# radio_module.net
KiCad netlist of a schematic drawn in EAGLE
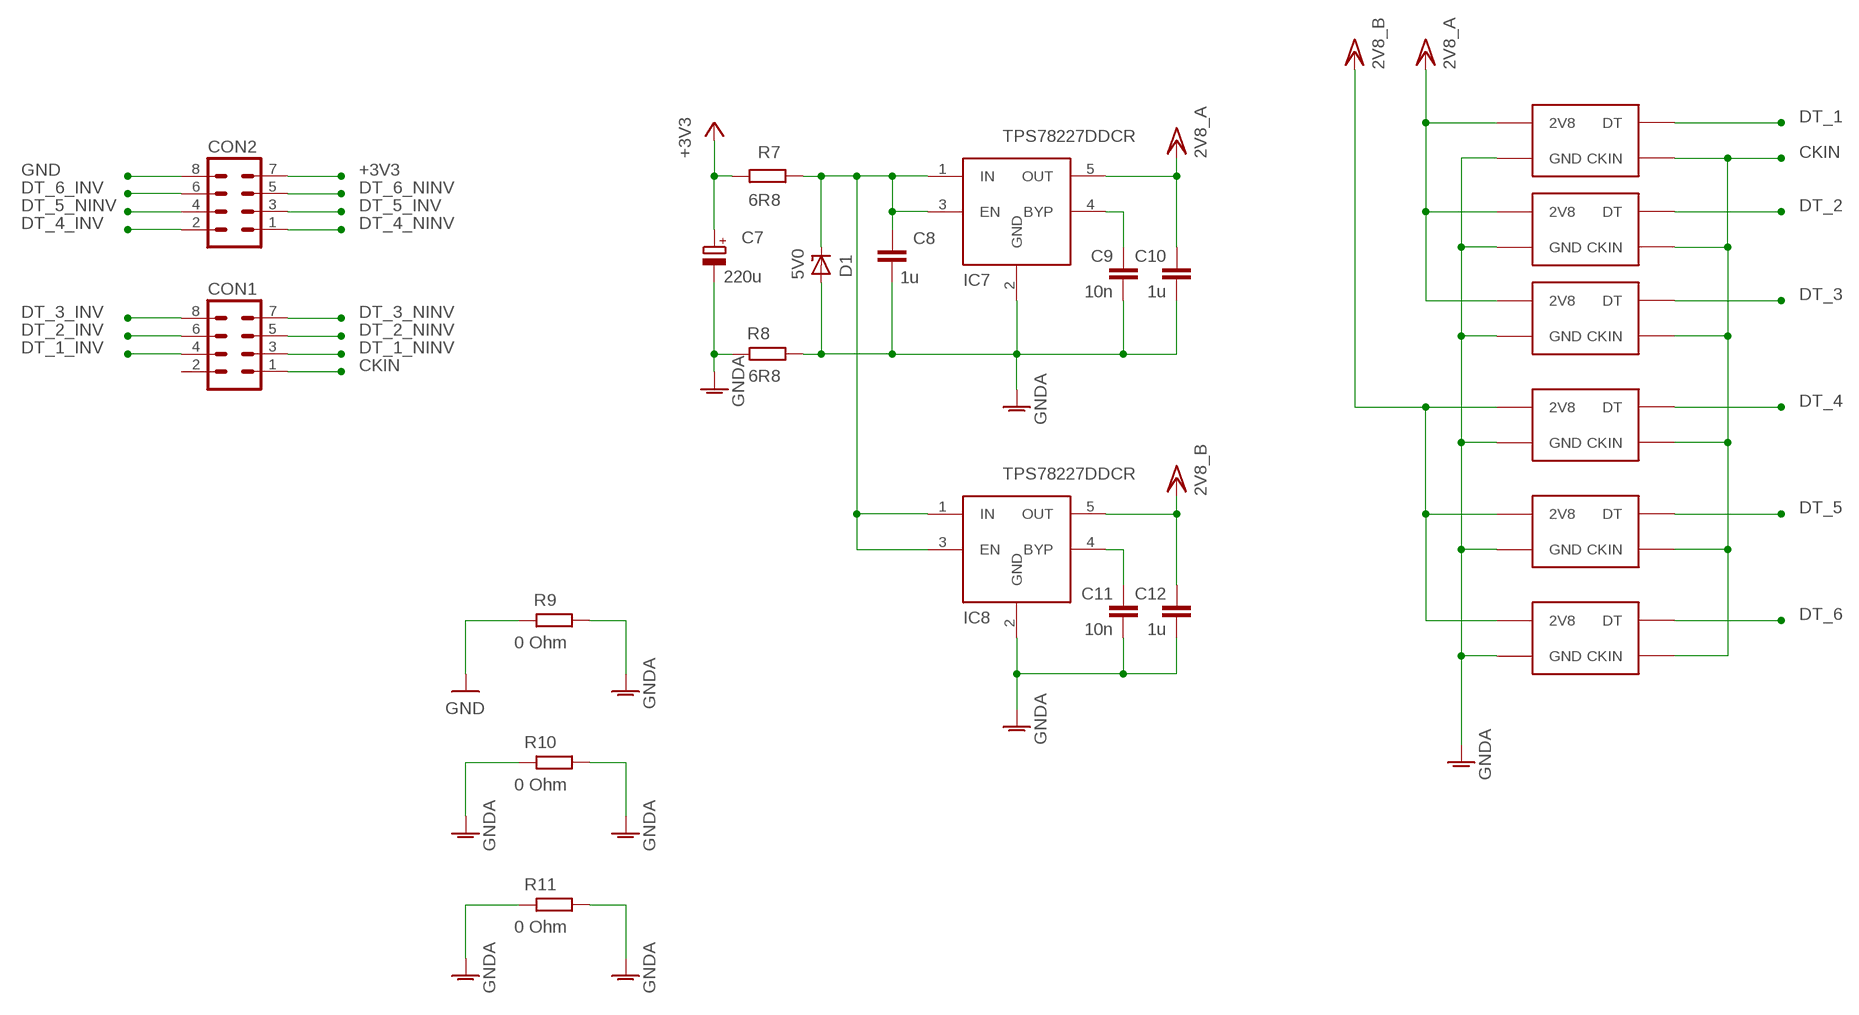
[diagram p0: schematic, sheet 1, part 1 of 2]
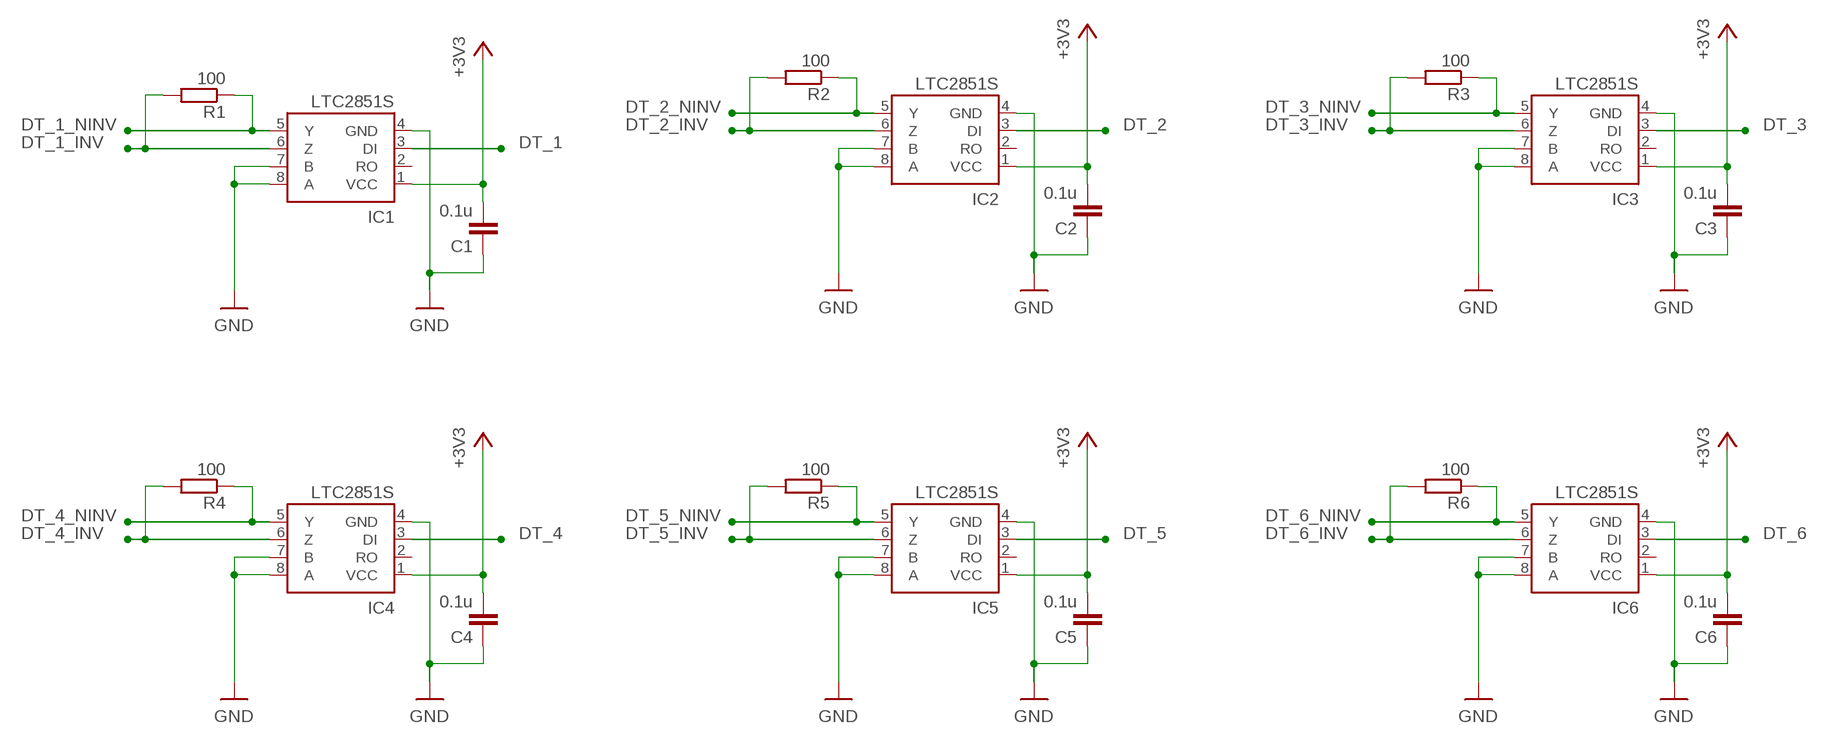
[diagram p1: schematic, sheet 1, part 2 of 2]

(export (version "E")
  (design (tool "Eeschema 10.0.6"))
  (components
    (comp (ref "C1")
      (value "0.1u")
      (footprint "eagle-import:C0805")
      (libsource (lib "eagle-import") (part "C-EUC0805"))
    )
    (comp (ref "C2")
      (value "0.1u")
      (footprint "eagle-import:C0805")
      (libsource (lib "eagle-import") (part "C-EUC0805"))
    )
    (comp (ref "C3")
      (value "0.1u")
      (footprint "eagle-import:C0805")
      (libsource (lib "eagle-import") (part "C-EUC0805"))
    )
    (comp (ref "C4")
      (value "0.1u")
      (footprint "eagle-import:C0805")
      (libsource (lib "eagle-import") (part "C-EUC0805"))
    )
    (comp (ref "C5")
      (value "0.1u")
      (footprint "eagle-import:C0805")
      (libsource (lib "eagle-import") (part "C-EUC0805"))
    )
    (comp (ref "C6")
      (value "0.1u")
      (footprint "eagle-import:C0805")
      (libsource (lib "eagle-import") (part "C-EUC0805"))
    )
    (comp (ref "C7")
      (value "220u")
      (footprint "eagle-import:C1210")
      (libsource (lib "eagle-import") (part "CPOL-EU1210"))
    )
    (comp (ref "C8")
      (value "1u")
      (footprint "eagle-import:C0603")
      (libsource (lib "eagle-import") (part "C-EUC0603"))
    )
    (comp (ref "C9")
      (value "10n")
      (footprint "eagle-import:C0603")
      (libsource (lib "eagle-import") (part "C-EUC0603"))
    )
    (comp (ref "C10")
      (value "1u")
      (footprint "eagle-import:C0603")
      (libsource (lib "eagle-import") (part "C-EUC0603"))
    )
    (comp (ref "C11")
      (value "10n")
      (footprint "eagle-import:C0603")
      (libsource (lib "eagle-import") (part "C-EUC0603"))
    )
    (comp (ref "C12")
      (value "1u")
      (footprint "eagle-import:C0603")
      (libsource (lib "eagle-import") (part "C-EUC0603"))
    )
    (comp (ref "CON1")
      (value "MA04-2")
      (footprint "eagle-import:MA04-2")
      (libsource (lib "eagle-import") (part "MA04-2"))
    )
    (comp (ref "CON2")
      (value "MA04-2")
      (footprint "eagle-import:MA04-2")
      (libsource (lib "eagle-import") (part "MA04-2"))
    )
    (comp (ref "D1")
      (value "5V0")
      (footprint "eagle-import:SOD523")
      (libsource (lib "eagle-import") (part "ZENER-DIODESOD523"))
    )
    (comp (ref "IC1")
      (value "LTC2851S")
      (footprint "eagle-import:SOIC8")
      (libsource (lib "eagle-import") (part "LTC2851S"))
    )
    (comp (ref "IC2")
      (value "LTC2851S")
      (footprint "eagle-import:SOIC8")
      (libsource (lib "eagle-import") (part "LTC2851S"))
    )
    (comp (ref "IC3")
      (value "LTC2851S")
      (footprint "eagle-import:SOIC8")
      (libsource (lib "eagle-import") (part "LTC2851S"))
    )
    (comp (ref "IC4")
      (value "LTC2851S")
      (footprint "eagle-import:SOIC8")
      (libsource (lib "eagle-import") (part "LTC2851S"))
    )
    (comp (ref "IC5")
      (value "LTC2851S")
      (footprint "eagle-import:SOIC8")
      (libsource (lib "eagle-import") (part "LTC2851S"))
    )
    (comp (ref "IC6")
      (value "LTC2851S")
      (footprint "eagle-import:SOIC8")
      (libsource (lib "eagle-import") (part "LTC2851S"))
    )
    (comp (ref "IC7")
      (value "TPS78227DDCR")
      (footprint "eagle-import:SOT23-5")
      (libsource (lib "eagle-import") (part "NCP700BSN"))
    )
    (comp (ref "IC8")
      (value "TPS78227DDCR")
      (footprint "eagle-import:SOT23-5")
      (libsource (lib "eagle-import") (part "NCP700BSN"))
    )
    (comp (ref "MOD_1")
      (value "GPS_RADIO_MODULE")
      (footprint "eagle-import:GPS_RADIO_MODULE")
      (libsource (lib "eagle-import") (part "GPS_RADIO_MODULE"))
    )
    (comp (ref "MOD_2")
      (value "GPS_RADIO_MODULE")
      (footprint "eagle-import:GPS_RADIO_MODULE")
      (libsource (lib "eagle-import") (part "GPS_RADIO_MODULE"))
    )
    (comp (ref "MOD_3")
      (value "GPS_RADIO_MODULE")
      (footprint "eagle-import:GPS_RADIO_MODULE")
      (libsource (lib "eagle-import") (part "GPS_RADIO_MODULE"))
    )
    (comp (ref "MOD_4")
      (value "GPS_RADIO_MODULE")
      (footprint "eagle-import:GPS_RADIO_MODULE")
      (libsource (lib "eagle-import") (part "GPS_RADIO_MODULE"))
    )
    (comp (ref "MOD_5")
      (value "GPS_RADIO_MODULE")
      (footprint "eagle-import:GPS_RADIO_MODULE")
      (libsource (lib "eagle-import") (part "GPS_RADIO_MODULE"))
    )
    (comp (ref "MOD_6")
      (value "GPS_RADIO_MODULE")
      (footprint "eagle-import:GPS_RADIO_MODULE")
      (libsource (lib "eagle-import") (part "GPS_RADIO_MODULE"))
    )
    (comp (ref "R1")
      (value "100")
      (footprint "eagle-import:R0603")
      (libsource (lib "eagle-import") (part "R-EU_R0603"))
    )
    (comp (ref "R2")
      (value "100")
      (footprint "eagle-import:R0603")
      (libsource (lib "eagle-import") (part "R-EU_R0603"))
    )
    (comp (ref "R3")
      (value "100")
      (footprint "eagle-import:R0603")
      (libsource (lib "eagle-import") (part "R-EU_R0603"))
    )
    (comp (ref "R4")
      (value "100")
      (footprint "eagle-import:R0603")
      (libsource (lib "eagle-import") (part "R-EU_R0603"))
    )
    (comp (ref "R5")
      (value "100")
      (footprint "eagle-import:R0603")
      (libsource (lib "eagle-import") (part "R-EU_R0603"))
    )
    (comp (ref "R6")
      (value "100")
      (footprint "eagle-import:R0603")
      (libsource (lib "eagle-import") (part "R-EU_R0603"))
    )
    (comp (ref "R7")
      (value "6R8")
      (footprint "eagle-import:R0805")
      (libsource (lib "eagle-import") (part "R-EU_R0805"))
    )
    (comp (ref "R8")
      (value "6R8")
      (footprint "eagle-import:R0603")
      (libsource (lib "eagle-import") (part "R-EU_R0603"))
    )
    (comp (ref "R9")
      (value "0 Ohm")
      (footprint "eagle-import:R0805")
      (libsource (lib "eagle-import") (part "R-EU_R0805"))
    )
    (comp (ref "R10")
      (value "0 Ohm")
      (footprint "eagle-import:R0805")
      (libsource (lib "eagle-import") (part "R-EU_R0805"))
    )
    (comp (ref "R11")
      (value "0 Ohm")
      (footprint "eagle-import:R0805")
      (libsource (lib "eagle-import") (part "R-EU_R0805"))
    )
  )
  (nets
    (net (code "1") (name "+3V3") (class "Default")
      (node (ref "C1") (pin "2") (pinfunction "2_2") (pintype "passive"))
      (node (ref "C2") (pin "2") (pinfunction "2_2") (pintype "passive"))
      (node (ref "C3") (pin "2") (pinfunction "2_2") (pintype "passive"))
      (node (ref "C4") (pin "2") (pinfunction "2_2") (pintype "passive"))
      (node (ref "C5") (pin "2") (pinfunction "2_2") (pintype "passive"))
      (node (ref "C6") (pin "2") (pinfunction "2_2") (pintype "passive"))
      (node (ref "C7") (pin "1") (pinfunction "+_1") (pintype "passive"))
      (node (ref "CON2") (pin "7") (pinfunction "7_7") (pintype "passive"))
      (node (ref "IC1") (pin "1") (pinfunction "VCC_1") (pintype "power_in"))
      (node (ref "IC2") (pin "1") (pinfunction "VCC_1") (pintype "power_in"))
      (node (ref "IC3") (pin "1") (pinfunction "VCC_1") (pintype "power_in"))
      (node (ref "IC4") (pin "1") (pinfunction "VCC_1") (pintype "power_in"))
      (node (ref "IC5") (pin "1") (pinfunction "VCC_1") (pintype "power_in"))
      (node (ref "IC6") (pin "1") (pinfunction "VCC_1") (pintype "power_in"))
      (node (ref "R7") (pin "2") (pinfunction "2_2") (pintype "passive"))
    )
    (net (code "2") (name "/CKIN") (class "Default")
      (node (ref "CON1") (pin "1") (pinfunction "1_1") (pintype "passive"))
      (node (ref "MOD_1") (pin "CKIN@13") (pinfunction "CKIN_CKIN@13") (pintype "input"))
      (node (ref "MOD_2") (pin "CKIN@13") (pinfunction "CKIN_CKIN@13") (pintype "input"))
      (node (ref "MOD_3") (pin "CKIN@13") (pinfunction "CKIN_CKIN@13") (pintype "input"))
      (node (ref "MOD_4") (pin "CKIN@13") (pinfunction "CKIN_CKIN@13") (pintype "input"))
      (node (ref "MOD_5") (pin "CKIN@13") (pinfunction "CKIN_CKIN@13") (pintype "input"))
      (node (ref "MOD_6") (pin "CKIN@13") (pinfunction "CKIN_CKIN@13") (pintype "input"))
    )
    (net (code "3") (name "/DT_1") (class "Default")
      (node (ref "IC1") (pin "3") (pinfunction "DI_3") (pintype "input"))
      (node (ref "MOD_1") (pin "DT@12") (pinfunction "DT_DT@12") (pintype "output"))
    )
    (net (code "4") (name "/DT_1_INV") (class "Default")
      (node (ref "CON1") (pin "4") (pinfunction "4_4") (pintype "passive"))
      (node (ref "IC1") (pin "6") (pinfunction "Z_6") (pintype "output"))
      (node (ref "R1") (pin "2") (pinfunction "2_2") (pintype "passive"))
    )
    (net (code "5") (name "/DT_1_NINV") (class "Default")
      (node (ref "CON1") (pin "3") (pinfunction "3_3") (pintype "passive"))
      (node (ref "IC1") (pin "5") (pinfunction "Y_5") (pintype "output"))
      (node (ref "R1") (pin "1") (pinfunction "1_1") (pintype "passive"))
    )
    (net (code "6") (name "/DT_2") (class "Default")
      (node (ref "IC2") (pin "3") (pinfunction "DI_3") (pintype "input"))
      (node (ref "MOD_2") (pin "DT@12") (pinfunction "DT_DT@12") (pintype "output"))
    )
    (net (code "7") (name "/DT_2_INV") (class "Default")
      (node (ref "CON1") (pin "6") (pinfunction "6_6") (pintype "passive"))
      (node (ref "IC2") (pin "6") (pinfunction "Z_6") (pintype "output"))
      (node (ref "R2") (pin "2") (pinfunction "2_2") (pintype "passive"))
    )
    (net (code "8") (name "/DT_2_NINV") (class "Default")
      (node (ref "CON1") (pin "5") (pinfunction "5_5") (pintype "passive"))
      (node (ref "IC2") (pin "5") (pinfunction "Y_5") (pintype "output"))
      (node (ref "R2") (pin "1") (pinfunction "1_1") (pintype "passive"))
    )
    (net (code "9") (name "/DT_3") (class "Default")
      (node (ref "IC3") (pin "3") (pinfunction "DI_3") (pintype "input"))
      (node (ref "MOD_3") (pin "DT@12") (pinfunction "DT_DT@12") (pintype "output"))
    )
    (net (code "10") (name "/DT_3_INV") (class "Default")
      (node (ref "CON1") (pin "8") (pinfunction "8_8") (pintype "passive"))
      (node (ref "IC3") (pin "6") (pinfunction "Z_6") (pintype "output"))
      (node (ref "R3") (pin "2") (pinfunction "2_2") (pintype "passive"))
    )
    (net (code "11") (name "/DT_3_NINV") (class "Default")
      (node (ref "CON1") (pin "7") (pinfunction "7_7") (pintype "passive"))
      (node (ref "IC3") (pin "5") (pinfunction "Y_5") (pintype "output"))
      (node (ref "R3") (pin "1") (pinfunction "1_1") (pintype "passive"))
    )
    (net (code "12") (name "/DT_4") (class "Default")
      (node (ref "IC4") (pin "3") (pinfunction "DI_3") (pintype "input"))
      (node (ref "MOD_6") (pin "DT@12") (pinfunction "DT_DT@12") (pintype "output"))
    )
    (net (code "13") (name "/DT_4_INV") (class "Default")
      (node (ref "CON2") (pin "2") (pinfunction "2_2") (pintype "passive"))
      (node (ref "IC4") (pin "6") (pinfunction "Z_6") (pintype "output"))
      (node (ref "R4") (pin "2") (pinfunction "2_2") (pintype "passive"))
    )
    (net (code "14") (name "/DT_4_NINV") (class "Default")
      (node (ref "CON2") (pin "1") (pinfunction "1_1") (pintype "passive"))
      (node (ref "IC4") (pin "5") (pinfunction "Y_5") (pintype "output"))
      (node (ref "R4") (pin "1") (pinfunction "1_1") (pintype "passive"))
    )
    (net (code "15") (name "/DT_5") (class "Default")
      (node (ref "IC5") (pin "3") (pinfunction "DI_3") (pintype "input"))
      (node (ref "MOD_5") (pin "DT@12") (pinfunction "DT_DT@12") (pintype "output"))
    )
    (net (code "16") (name "/DT_5_INV") (class "Default")
      (node (ref "CON2") (pin "3") (pinfunction "3_3") (pintype "passive"))
      (node (ref "IC5") (pin "6") (pinfunction "Z_6") (pintype "output"))
      (node (ref "R5") (pin "2") (pinfunction "2_2") (pintype "passive"))
    )
    (net (code "17") (name "/DT_5_NINV") (class "Default")
      (node (ref "CON2") (pin "4") (pinfunction "4_4") (pintype "passive"))
      (node (ref "IC5") (pin "5") (pinfunction "Y_5") (pintype "output"))
      (node (ref "R5") (pin "1") (pinfunction "1_1") (pintype "passive"))
    )
    (net (code "18") (name "/DT_6") (class "Default")
      (node (ref "IC6") (pin "3") (pinfunction "DI_3") (pintype "input"))
      (node (ref "MOD_4") (pin "DT@12") (pinfunction "DT_DT@12") (pintype "output"))
    )
    (net (code "19") (name "/DT_6_INV") (class "Default")
      (node (ref "CON2") (pin "6") (pinfunction "6_6") (pintype "passive"))
      (node (ref "IC6") (pin "6") (pinfunction "Z_6") (pintype "output"))
      (node (ref "R6") (pin "2") (pinfunction "2_2") (pintype "passive"))
    )
    (net (code "20") (name "/DT_6_NINV") (class "Default")
      (node (ref "CON2") (pin "5") (pinfunction "5_5") (pintype "passive"))
      (node (ref "IC6") (pin "5") (pinfunction "Y_5") (pintype "output"))
      (node (ref "R6") (pin "1") (pinfunction "1_1") (pintype "passive"))
    )
    (net (code "21") (name "2V8_A") (class "Default")
      (node (ref "C10") (pin "1") (pinfunction "1_1") (pintype "passive"))
      (node (ref "IC7") (pin "5") (pinfunction "OUT_5") (pintype "power_in"))
      (node (ref "MOD_1") (pin "2V8@11") (pinfunction "2V8_2V8@11") (pintype "power_in"))
      (node (ref "MOD_1") (pin "2V8@15") (pinfunction "2V8_2V8@15") (pintype "power_in"))
      (node (ref "MOD_1") (pin "2V8@16") (pinfunction "2V8_2V8@16") (pintype "power_in"))
      (node (ref "MOD_2") (pin "2V8@11") (pinfunction "2V8_2V8@11") (pintype "power_in"))
      (node (ref "MOD_2") (pin "2V8@15") (pinfunction "2V8_2V8@15") (pintype "power_in"))
      (node (ref "MOD_2") (pin "2V8@16") (pinfunction "2V8_2V8@16") (pintype "power_in"))
      (node (ref "MOD_3") (pin "2V8@11") (pinfunction "2V8_2V8@11") (pintype "power_in"))
      (node (ref "MOD_3") (pin "2V8@15") (pinfunction "2V8_2V8@15") (pintype "power_in"))
      (node (ref "MOD_3") (pin "2V8@16") (pinfunction "2V8_2V8@16") (pintype "power_in"))
    )
    (net (code "22") (name "2V8_B") (class "Default")
      (node (ref "C12") (pin "1") (pinfunction "1_1") (pintype "passive"))
      (node (ref "IC8") (pin "5") (pinfunction "OUT_5") (pintype "power_in"))
      (node (ref "MOD_4") (pin "2V8@11") (pinfunction "2V8_2V8@11") (pintype "power_in"))
      (node (ref "MOD_4") (pin "2V8@15") (pinfunction "2V8_2V8@15") (pintype "power_in"))
      (node (ref "MOD_4") (pin "2V8@16") (pinfunction "2V8_2V8@16") (pintype "power_in"))
      (node (ref "MOD_5") (pin "2V8@11") (pinfunction "2V8_2V8@11") (pintype "power_in"))
      (node (ref "MOD_5") (pin "2V8@15") (pinfunction "2V8_2V8@15") (pintype "power_in"))
      (node (ref "MOD_5") (pin "2V8@16") (pinfunction "2V8_2V8@16") (pintype "power_in"))
      (node (ref "MOD_6") (pin "2V8@11") (pinfunction "2V8_2V8@11") (pintype "power_in"))
      (node (ref "MOD_6") (pin "2V8@15") (pinfunction "2V8_2V8@15") (pintype "power_in"))
      (node (ref "MOD_6") (pin "2V8@16") (pinfunction "2V8_2V8@16") (pintype "power_in"))
    )
    (net (code "23") (name "GND") (class "Default")
      (node (ref "C1") (pin "1") (pinfunction "1_1") (pintype "passive"))
      (node (ref "C2") (pin "1") (pinfunction "1_1") (pintype "passive"))
      (node (ref "C3") (pin "1") (pinfunction "1_1") (pintype "passive"))
      (node (ref "C4") (pin "1") (pinfunction "1_1") (pintype "passive"))
      (node (ref "C5") (pin "1") (pinfunction "1_1") (pintype "passive"))
      (node (ref "C6") (pin "1") (pinfunction "1_1") (pintype "passive"))
      (node (ref "CON2") (pin "8") (pinfunction "8_8") (pintype "passive"))
      (node (ref "IC1") (pin "4") (pinfunction "GND_4") (pintype "power_in"))
      (node (ref "IC1") (pin "7") (pinfunction "B_7") (pintype "input"))
      (node (ref "IC1") (pin "8") (pinfunction "A_8") (pintype "input"))
      (node (ref "IC2") (pin "4") (pinfunction "GND_4") (pintype "power_in"))
      (node (ref "IC2") (pin "7") (pinfunction "B_7") (pintype "input"))
      (node (ref "IC2") (pin "8") (pinfunction "A_8") (pintype "input"))
      (node (ref "IC3") (pin "4") (pinfunction "GND_4") (pintype "power_in"))
      (node (ref "IC3") (pin "7") (pinfunction "B_7") (pintype "input"))
      (node (ref "IC3") (pin "8") (pinfunction "A_8") (pintype "input"))
      (node (ref "IC4") (pin "4") (pinfunction "GND_4") (pintype "power_in"))
      (node (ref "IC4") (pin "7") (pinfunction "B_7") (pintype "input"))
      (node (ref "IC4") (pin "8") (pinfunction "A_8") (pintype "input"))
      (node (ref "IC5") (pin "4") (pinfunction "GND_4") (pintype "power_in"))
      (node (ref "IC5") (pin "7") (pinfunction "B_7") (pintype "input"))
      (node (ref "IC5") (pin "8") (pinfunction "A_8") (pintype "input"))
      (node (ref "IC6") (pin "4") (pinfunction "GND_4") (pintype "power_in"))
      (node (ref "IC6") (pin "7") (pinfunction "B_7") (pintype "input"))
      (node (ref "IC6") (pin "8") (pinfunction "A_8") (pintype "input"))
      (node (ref "R9") (pin "2") (pinfunction "2_2") (pintype "passive"))
    )
    (net (code "24") (name "GNDA") (class "Default")
      (node (ref "C10") (pin "2") (pinfunction "2_2") (pintype "passive"))
      (node (ref "C11") (pin "2") (pinfunction "2_2") (pintype "passive"))
      (node (ref "C12") (pin "2") (pinfunction "2_2") (pintype "passive"))
      (node (ref "C7") (pin "2") (pinfunction "-_2") (pintype "passive"))
      (node (ref "C8") (pin "2") (pinfunction "2_2") (pintype "passive"))
      (node (ref "C9") (pin "2") (pinfunction "2_2") (pintype "passive"))
      (node (ref "D1") (pin "A") (pinfunction "A_A") (pintype "passive"))
      (node (ref "IC7") (pin "2") (pinfunction "GND_2") (pintype "power_in"))
      (node (ref "IC8") (pin "2") (pinfunction "GND_2") (pintype "power_in"))
      (node (ref "MOD_1") (pin "GND@1") (pinfunction "GND_GND@1") (pintype "power_in"))
      (node (ref "MOD_1") (pin "GND@10") (pinfunction "GND_GND@10") (pintype "power_in"))
      (node (ref "MOD_1") (pin "GND@14") (pinfunction "GND_GND@14") (pintype "power_in"))
      (node (ref "MOD_1") (pin "GND@2") (pinfunction "GND_GND@2") (pintype "power_in"))
      (node (ref "MOD_1") (pin "GND@3") (pinfunction "GND_GND@3") (pintype "power_in"))
      (node (ref "MOD_1") (pin "GND@4") (pinfunction "GND_GND@4") (pintype "power_in"))
      (node (ref "MOD_1") (pin "GND@5") (pinfunction "GND_GND@5") (pintype "power_in"))
      (node (ref "MOD_1") (pin "GND@6") (pinfunction "GND_GND@6") (pintype "power_in"))
      (node (ref "MOD_1") (pin "GND@7") (pinfunction "GND_GND@7") (pintype "power_in"))
      (node (ref "MOD_1") (pin "GND@8") (pinfunction "GND_GND@8") (pintype "power_in"))
      (node (ref "MOD_1") (pin "GND@9") (pinfunction "GND_GND@9") (pintype "power_in"))
      (node (ref "MOD_1") (pin "V1") (pinfunction "GND_V1") (pintype "power_in"))
      (node (ref "MOD_1") (pin "V10") (pinfunction "GND_V10") (pintype "power_in"))
      (node (ref "MOD_1") (pin "V11") (pinfunction "GND_V11") (pintype "power_in"))
      (node (ref "MOD_1") (pin "V12") (pinfunction "GND_V12") (pintype "power_in"))
      (node (ref "MOD_1") (pin "V13") (pinfunction "GND_V13") (pintype "power_in"))
      (node (ref "MOD_1") (pin "V14") (pinfunction "GND_V14") (pintype "power_in"))
      (node (ref "MOD_1") (pin "V15") (pinfunction "GND_V15") (pintype "power_in"))
      (node (ref "MOD_1") (pin "V16") (pinfunction "GND_V16") (pintype "power_in"))
      (node (ref "MOD_1") (pin "V17") (pinfunction "GND_V17") (pintype "power_in"))
      (node (ref "MOD_1") (pin "V18") (pinfunction "GND_V18") (pintype "power_in"))
      (node (ref "MOD_1") (pin "V19") (pinfunction "GND_V19") (pintype "power_in"))
      (node (ref "MOD_1") (pin "V2") (pinfunction "GND_V2") (pintype "power_in"))
      (node (ref "MOD_1") (pin "V20") (pinfunction "GND_V20") (pintype "power_in"))
      (node (ref "MOD_1") (pin "V21") (pinfunction "GND_V21") (pintype "power_in"))
      (node (ref "MOD_1") (pin "V22") (pinfunction "GND_V22") (pintype "power_in"))
      (node (ref "MOD_1") (pin "V23") (pinfunction "GND_V23") (pintype "power_in"))
      (node (ref "MOD_1") (pin "V24") (pinfunction "GND_V24") (pintype "power_in"))
      (node (ref "MOD_1") (pin "V25") (pinfunction "GND_V25") (pintype "power_in"))
      (node (ref "MOD_1") (pin "V26") (pinfunction "GND_V26") (pintype "power_in"))
      (node (ref "MOD_1") (pin "V27") (pinfunction "GND_V27") (pintype "power_in"))
      (node (ref "MOD_1") (pin "V28") (pinfunction "GND_V28") (pintype "power_in"))
      (node (ref "MOD_1") (pin "V29") (pinfunction "GND_V29") (pintype "power_in"))
      (node (ref "MOD_1") (pin "V3") (pinfunction "GND_V3") (pintype "power_in"))
      (node (ref "MOD_1") (pin "V30") (pinfunction "GND_V30") (pintype "power_in"))
      (node (ref "MOD_1") (pin "V4") (pinfunction "GND_V4") (pintype "power_in"))
      (node (ref "MOD_1") (pin "V5") (pinfunction "GND_V5") (pintype "power_in"))
      (node (ref "MOD_1") (pin "V6") (pinfunction "GND_V6") (pintype "power_in"))
      (node (ref "MOD_1") (pin "V7") (pinfunction "GND_V7") (pintype "power_in"))
      (node (ref "MOD_1") (pin "V8") (pinfunction "GND_V8") (pintype "power_in"))
      (node (ref "MOD_1") (pin "V9") (pinfunction "GND_V9") (pintype "power_in"))
      (node (ref "MOD_2") (pin "GND@1") (pinfunction "GND_GND@1") (pintype "power_in"))
      (node (ref "MOD_2") (pin "GND@10") (pinfunction "GND_GND@10") (pintype "power_in"))
      (node (ref "MOD_2") (pin "GND@14") (pinfunction "GND_GND@14") (pintype "power_in"))
      (node (ref "MOD_2") (pin "GND@2") (pinfunction "GND_GND@2") (pintype "power_in"))
      (node (ref "MOD_2") (pin "GND@3") (pinfunction "GND_GND@3") (pintype "power_in"))
      (node (ref "MOD_2") (pin "GND@4") (pinfunction "GND_GND@4") (pintype "power_in"))
      (node (ref "MOD_2") (pin "GND@5") (pinfunction "GND_GND@5") (pintype "power_in"))
      (node (ref "MOD_2") (pin "GND@6") (pinfunction "GND_GND@6") (pintype "power_in"))
      (node (ref "MOD_2") (pin "GND@7") (pinfunction "GND_GND@7") (pintype "power_in"))
      (node (ref "MOD_2") (pin "GND@8") (pinfunction "GND_GND@8") (pintype "power_in"))
      (node (ref "MOD_2") (pin "GND@9") (pinfunction "GND_GND@9") (pintype "power_in"))
      (node (ref "MOD_2") (pin "V1") (pinfunction "GND_V1") (pintype "power_in"))
      (node (ref "MOD_2") (pin "V10") (pinfunction "GND_V10") (pintype "power_in"))
      (node (ref "MOD_2") (pin "V11") (pinfunction "GND_V11") (pintype "power_in"))
      (node (ref "MOD_2") (pin "V12") (pinfunction "GND_V12") (pintype "power_in"))
      (node (ref "MOD_2") (pin "V13") (pinfunction "GND_V13") (pintype "power_in"))
      (node (ref "MOD_2") (pin "V14") (pinfunction "GND_V14") (pintype "power_in"))
      (node (ref "MOD_2") (pin "V15") (pinfunction "GND_V15") (pintype "power_in"))
      (node (ref "MOD_2") (pin "V16") (pinfunction "GND_V16") (pintype "power_in"))
      (node (ref "MOD_2") (pin "V17") (pinfunction "GND_V17") (pintype "power_in"))
      (node (ref "MOD_2") (pin "V18") (pinfunction "GND_V18") (pintype "power_in"))
      (node (ref "MOD_2") (pin "V19") (pinfunction "GND_V19") (pintype "power_in"))
      (node (ref "MOD_2") (pin "V2") (pinfunction "GND_V2") (pintype "power_in"))
      (node (ref "MOD_2") (pin "V20") (pinfunction "GND_V20") (pintype "power_in"))
      (node (ref "MOD_2") (pin "V21") (pinfunction "GND_V21") (pintype "power_in"))
      (node (ref "MOD_2") (pin "V22") (pinfunction "GND_V22") (pintype "power_in"))
      (node (ref "MOD_2") (pin "V23") (pinfunction "GND_V23") (pintype "power_in"))
      (node (ref "MOD_2") (pin "V24") (pinfunction "GND_V24") (pintype "power_in"))
      (node (ref "MOD_2") (pin "V25") (pinfunction "GND_V25") (pintype "power_in"))
      (node (ref "MOD_2") (pin "V26") (pinfunction "GND_V26") (pintype "power_in"))
      (node (ref "MOD_2") (pin "V27") (pinfunction "GND_V27") (pintype "power_in"))
      (node (ref "MOD_2") (pin "V28") (pinfunction "GND_V28") (pintype "power_in"))
      (node (ref "MOD_2") (pin "V29") (pinfunction "GND_V29") (pintype "power_in"))
      (node (ref "MOD_2") (pin "V3") (pinfunction "GND_V3") (pintype "power_in"))
      (node (ref "MOD_2") (pin "V30") (pinfunction "GND_V30") (pintype "power_in"))
      (node (ref "MOD_2") (pin "V4") (pinfunction "GND_V4") (pintype "power_in"))
      (node (ref "MOD_2") (pin "V5") (pinfunction "GND_V5") (pintype "power_in"))
      (node (ref "MOD_2") (pin "V6") (pinfunction "GND_V6") (pintype "power_in"))
      (node (ref "MOD_2") (pin "V7") (pinfunction "GND_V7") (pintype "power_in"))
      (node (ref "MOD_2") (pin "V8") (pinfunction "GND_V8") (pintype "power_in"))
      (node (ref "MOD_2") (pin "V9") (pinfunction "GND_V9") (pintype "power_in"))
      (node (ref "MOD_3") (pin "GND@1") (pinfunction "GND_GND@1") (pintype "power_in"))
      (node (ref "MOD_3") (pin "GND@10") (pinfunction "GND_GND@10") (pintype "power_in"))
      (node (ref "MOD_3") (pin "GND@14") (pinfunction "GND_GND@14") (pintype "power_in"))
      (node (ref "MOD_3") (pin "GND@2") (pinfunction "GND_GND@2") (pintype "power_in"))
      (node (ref "MOD_3") (pin "GND@3") (pinfunction "GND_GND@3") (pintype "power_in"))
      (node (ref "MOD_3") (pin "GND@4") (pinfunction "GND_GND@4") (pintype "power_in"))
      (node (ref "MOD_3") (pin "GND@5") (pinfunction "GND_GND@5") (pintype "power_in"))
      (node (ref "MOD_3") (pin "GND@6") (pinfunction "GND_GND@6") (pintype "power_in"))
      (node (ref "MOD_3") (pin "GND@7") (pinfunction "GND_GND@7") (pintype "power_in"))
      (node (ref "MOD_3") (pin "GND@8") (pinfunction "GND_GND@8") (pintype "power_in"))
      (node (ref "MOD_3") (pin "GND@9") (pinfunction "GND_GND@9") (pintype "power_in"))
      (node (ref "MOD_3") (pin "V1") (pinfunction "GND_V1") (pintype "power_in"))
      (node (ref "MOD_3") (pin "V10") (pinfunction "GND_V10") (pintype "power_in"))
      (node (ref "MOD_3") (pin "V11") (pinfunction "GND_V11") (pintype "power_in"))
      (node (ref "MOD_3") (pin "V12") (pinfunction "GND_V12") (pintype "power_in"))
      (node (ref "MOD_3") (pin "V13") (pinfunction "GND_V13") (pintype "power_in"))
      (node (ref "MOD_3") (pin "V14") (pinfunction "GND_V14") (pintype "power_in"))
      (node (ref "MOD_3") (pin "V15") (pinfunction "GND_V15") (pintype "power_in"))
      (node (ref "MOD_3") (pin "V16") (pinfunction "GND_V16") (pintype "power_in"))
      (node (ref "MOD_3") (pin "V17") (pinfunction "GND_V17") (pintype "power_in"))
      (node (ref "MOD_3") (pin "V18") (pinfunction "GND_V18") (pintype "power_in"))
      (node (ref "MOD_3") (pin "V19") (pinfunction "GND_V19") (pintype "power_in"))
      (node (ref "MOD_3") (pin "V2") (pinfunction "GND_V2") (pintype "power_in"))
      (node (ref "MOD_3") (pin "V20") (pinfunction "GND_V20") (pintype "power_in"))
      (node (ref "MOD_3") (pin "V21") (pinfunction "GND_V21") (pintype "power_in"))
      (node (ref "MOD_3") (pin "V22") (pinfunction "GND_V22") (pintype "power_in"))
      (node (ref "MOD_3") (pin "V23") (pinfunction "GND_V23") (pintype "power_in"))
      (node (ref "MOD_3") (pin "V24") (pinfunction "GND_V24") (pintype "power_in"))
      (node (ref "MOD_3") (pin "V25") (pinfunction "GND_V25") (pintype "power_in"))
      (node (ref "MOD_3") (pin "V26") (pinfunction "GND_V26") (pintype "power_in"))
      (node (ref "MOD_3") (pin "V27") (pinfunction "GND_V27") (pintype "power_in"))
      (node (ref "MOD_3") (pin "V28") (pinfunction "GND_V28") (pintype "power_in"))
      (node (ref "MOD_3") (pin "V29") (pinfunction "GND_V29") (pintype "power_in"))
      (node (ref "MOD_3") (pin "V3") (pinfunction "GND_V3") (pintype "power_in"))
      (node (ref "MOD_3") (pin "V30") (pinfunction "GND_V30") (pintype "power_in"))
      (node (ref "MOD_3") (pin "V4") (pinfunction "GND_V4") (pintype "power_in"))
      (node (ref "MOD_3") (pin "V5") (pinfunction "GND_V5") (pintype "power_in"))
      (node (ref "MOD_3") (pin "V6") (pinfunction "GND_V6") (pintype "power_in"))
      (node (ref "MOD_3") (pin "V7") (pinfunction "GND_V7") (pintype "power_in"))
      (node (ref "MOD_3") (pin "V8") (pinfunction "GND_V8") (pintype "power_in"))
      (node (ref "MOD_3") (pin "V9") (pinfunction "GND_V9") (pintype "power_in"))
      (node (ref "MOD_4") (pin "GND@1") (pinfunction "GND_GND@1") (pintype "power_in"))
      (node (ref "MOD_4") (pin "GND@10") (pinfunction "GND_GND@10") (pintype "power_in"))
      (node (ref "MOD_4") (pin "GND@14") (pinfunction "GND_GND@14") (pintype "power_in"))
      (node (ref "MOD_4") (pin "GND@2") (pinfunction "GND_GND@2") (pintype "power_in"))
      (node (ref "MOD_4") (pin "GND@3") (pinfunction "GND_GND@3") (pintype "power_in"))
      (node (ref "MOD_4") (pin "GND@4") (pinfunction "GND_GND@4") (pintype "power_in"))
      (node (ref "MOD_4") (pin "GND@5") (pinfunction "GND_GND@5") (pintype "power_in"))
      (node (ref "MOD_4") (pin "GND@6") (pinfunction "GND_GND@6") (pintype "power_in"))
      (node (ref "MOD_4") (pin "GND@7") (pinfunction "GND_GND@7") (pintype "power_in"))
      (node (ref "MOD_4") (pin "GND@8") (pinfunction "GND_GND@8") (pintype "power_in"))
      (node (ref "MOD_4") (pin "GND@9") (pinfunction "GND_GND@9") (pintype "power_in"))
      (node (ref "MOD_4") (pin "V1") (pinfunction "GND_V1") (pintype "power_in"))
      (node (ref "MOD_4") (pin "V10") (pinfunction "GND_V10") (pintype "power_in"))
      (node (ref "MOD_4") (pin "V11") (pinfunction "GND_V11") (pintype "power_in"))
      (node (ref "MOD_4") (pin "V12") (pinfunction "GND_V12") (pintype "power_in"))
      (node (ref "MOD_4") (pin "V13") (pinfunction "GND_V13") (pintype "power_in"))
      (node (ref "MOD_4") (pin "V14") (pinfunction "GND_V14") (pintype "power_in"))
      (node (ref "MOD_4") (pin "V15") (pinfunction "GND_V15") (pintype "power_in"))
      (node (ref "MOD_4") (pin "V16") (pinfunction "GND_V16") (pintype "power_in"))
      (node (ref "MOD_4") (pin "V17") (pinfunction "GND_V17") (pintype "power_in"))
      (node (ref "MOD_4") (pin "V18") (pinfunction "GND_V18") (pintype "power_in"))
      (node (ref "MOD_4") (pin "V19") (pinfunction "GND_V19") (pintype "power_in"))
      (node (ref "MOD_4") (pin "V2") (pinfunction "GND_V2") (pintype "power_in"))
      (node (ref "MOD_4") (pin "V20") (pinfunction "GND_V20") (pintype "power_in"))
      (node (ref "MOD_4") (pin "V21") (pinfunction "GND_V21") (pintype "power_in"))
      (node (ref "MOD_4") (pin "V22") (pinfunction "GND_V22") (pintype "power_in"))
      (node (ref "MOD_4") (pin "V23") (pinfunction "GND_V23") (pintype "power_in"))
      (node (ref "MOD_4") (pin "V24") (pinfunction "GND_V24") (pintype "power_in"))
      (node (ref "MOD_4") (pin "V25") (pinfunction "GND_V25") (pintype "power_in"))
      (node (ref "MOD_4") (pin "V26") (pinfunction "GND_V26") (pintype "power_in"))
      (node (ref "MOD_4") (pin "V27") (pinfunction "GND_V27") (pintype "power_in"))
      (node (ref "MOD_4") (pin "V28") (pinfunction "GND_V28") (pintype "power_in"))
      (node (ref "MOD_4") (pin "V29") (pinfunction "GND_V29") (pintype "power_in"))
      (node (ref "MOD_4") (pin "V3") (pinfunction "GND_V3") (pintype "power_in"))
      (node (ref "MOD_4") (pin "V30") (pinfunction "GND_V30") (pintype "power_in"))
      (node (ref "MOD_4") (pin "V4") (pinfunction "GND_V4") (pintype "power_in"))
      (node (ref "MOD_4") (pin "V5") (pinfunction "GND_V5") (pintype "power_in"))
      (node (ref "MOD_4") (pin "V6") (pinfunction "GND_V6") (pintype "power_in"))
      (node (ref "MOD_4") (pin "V7") (pinfunction "GND_V7") (pintype "power_in"))
      (node (ref "MOD_4") (pin "V8") (pinfunction "GND_V8") (pintype "power_in"))
      (node (ref "MOD_4") (pin "V9") (pinfunction "GND_V9") (pintype "power_in"))
      (node (ref "MOD_5") (pin "GND@1") (pinfunction "GND_GND@1") (pintype "power_in"))
      (node (ref "MOD_5") (pin "GND@10") (pinfunction "GND_GND@10") (pintype "power_in"))
      (node (ref "MOD_5") (pin "GND@14") (pinfunction "GND_GND@14") (pintype "power_in"))
      (node (ref "MOD_5") (pin "GND@2") (pinfunction "GND_GND@2") (pintype "power_in"))
      (node (ref "MOD_5") (pin "GND@3") (pinfunction "GND_GND@3") (pintype "power_in"))
      (node (ref "MOD_5") (pin "GND@4") (pinfunction "GND_GND@4") (pintype "power_in"))
      (node (ref "MOD_5") (pin "GND@5") (pinfunction "GND_GND@5") (pintype "power_in"))
      (node (ref "MOD_5") (pin "GND@6") (pinfunction "GND_GND@6") (pintype "power_in"))
      (node (ref "MOD_5") (pin "GND@7") (pinfunction "GND_GND@7") (pintype "power_in"))
      (node (ref "MOD_5") (pin "GND@8") (pinfunction "GND_GND@8") (pintype "power_in"))
      (node (ref "MOD_5") (pin "GND@9") (pinfunction "GND_GND@9") (pintype "power_in"))
      (node (ref "MOD_5") (pin "V1") (pinfunction "GND_V1") (pintype "power_in"))
      (node (ref "MOD_5") (pin "V10") (pinfunction "GND_V10") (pintype "power_in"))
      (node (ref "MOD_5") (pin "V11") (pinfunction "GND_V11") (pintype "power_in"))
      (node (ref "MOD_5") (pin "V12") (pinfunction "GND_V12") (pintype "power_in"))
      (node (ref "MOD_5") (pin "V13") (pinfunction "GND_V13") (pintype "power_in"))
      (node (ref "MOD_5") (pin "V14") (pinfunction "GND_V14") (pintype "power_in"))
      (node (ref "MOD_5") (pin "V15") (pinfunction "GND_V15") (pintype "power_in"))
      (node (ref "MOD_5") (pin "V16") (pinfunction "GND_V16") (pintype "power_in"))
      (node (ref "MOD_5") (pin "V17") (pinfunction "GND_V17") (pintype "power_in"))
      (node (ref "MOD_5") (pin "V18") (pinfunction "GND_V18") (pintype "power_in"))
      (node (ref "MOD_5") (pin "V19") (pinfunction "GND_V19") (pintype "power_in"))
      (node (ref "MOD_5") (pin "V2") (pinfunction "GND_V2") (pintype "power_in"))
      (node (ref "MOD_5") (pin "V20") (pinfunction "GND_V20") (pintype "power_in"))
      (node (ref "MOD_5") (pin "V21") (pinfunction "GND_V21") (pintype "power_in"))
      (node (ref "MOD_5") (pin "V22") (pinfunction "GND_V22") (pintype "power_in"))
      (node (ref "MOD_5") (pin "V23") (pinfunction "GND_V23") (pintype "power_in"))
      (node (ref "MOD_5") (pin "V24") (pinfunction "GND_V24") (pintype "power_in"))
      (node (ref "MOD_5") (pin "V25") (pinfunction "GND_V25") (pintype "power_in"))
      (node (ref "MOD_5") (pin "V26") (pinfunction "GND_V26") (pintype "power_in"))
      (node (ref "MOD_5") (pin "V27") (pinfunction "GND_V27") (pintype "power_in"))
      (node (ref "MOD_5") (pin "V28") (pinfunction "GND_V28") (pintype "power_in"))
      (node (ref "MOD_5") (pin "V29") (pinfunction "GND_V29") (pintype "power_in"))
      (node (ref "MOD_5") (pin "V3") (pinfunction "GND_V3") (pintype "power_in"))
      (node (ref "MOD_5") (pin "V30") (pinfunction "GND_V30") (pintype "power_in"))
      (node (ref "MOD_5") (pin "V4") (pinfunction "GND_V4") (pintype "power_in"))
      (node (ref "MOD_5") (pin "V5") (pinfunction "GND_V5") (pintype "power_in"))
      (node (ref "MOD_5") (pin "V6") (pinfunction "GND_V6") (pintype "power_in"))
      (node (ref "MOD_5") (pin "V7") (pinfunction "GND_V7") (pintype "power_in"))
      (node (ref "MOD_5") (pin "V8") (pinfunction "GND_V8") (pintype "power_in"))
      (node (ref "MOD_5") (pin "V9") (pinfunction "GND_V9") (pintype "power_in"))
      (node (ref "MOD_6") (pin "GND@1") (pinfunction "GND_GND@1") (pintype "power_in"))
      (node (ref "MOD_6") (pin "GND@10") (pinfunction "GND_GND@10") (pintype "power_in"))
      (node (ref "MOD_6") (pin "GND@14") (pinfunction "GND_GND@14") (pintype "power_in"))
      (node (ref "MOD_6") (pin "GND@2") (pinfunction "GND_GND@2") (pintype "power_in"))
      (node (ref "MOD_6") (pin "GND@3") (pinfunction "GND_GND@3") (pintype "power_in"))
      (node (ref "MOD_6") (pin "GND@4") (pinfunction "GND_GND@4") (pintype "power_in"))
      (node (ref "MOD_6") (pin "GND@5") (pinfunction "GND_GND@5") (pintype "power_in"))
      (node (ref "MOD_6") (pin "GND@6") (pinfunction "GND_GND@6") (pintype "power_in"))
      (node (ref "MOD_6") (pin "GND@7") (pinfunction "GND_GND@7") (pintype "power_in"))
      (node (ref "MOD_6") (pin "GND@8") (pinfunction "GND_GND@8") (pintype "power_in"))
      (node (ref "MOD_6") (pin "GND@9") (pinfunction "GND_GND@9") (pintype "power_in"))
      (node (ref "MOD_6") (pin "V1") (pinfunction "GND_V1") (pintype "power_in"))
      (node (ref "MOD_6") (pin "V10") (pinfunction "GND_V10") (pintype "power_in"))
      (node (ref "MOD_6") (pin "V11") (pinfunction "GND_V11") (pintype "power_in"))
      (node (ref "MOD_6") (pin "V12") (pinfunction "GND_V12") (pintype "power_in"))
      (node (ref "MOD_6") (pin "V13") (pinfunction "GND_V13") (pintype "power_in"))
      (node (ref "MOD_6") (pin "V14") (pinfunction "GND_V14") (pintype "power_in"))
      (node (ref "MOD_6") (pin "V15") (pinfunction "GND_V15") (pintype "power_in"))
      (node (ref "MOD_6") (pin "V16") (pinfunction "GND_V16") (pintype "power_in"))
      (node (ref "MOD_6") (pin "V17") (pinfunction "GND_V17") (pintype "power_in"))
      (node (ref "MOD_6") (pin "V18") (pinfunction "GND_V18") (pintype "power_in"))
      (node (ref "MOD_6") (pin "V19") (pinfunction "GND_V19") (pintype "power_in"))
      (node (ref "MOD_6") (pin "V2") (pinfunction "GND_V2") (pintype "power_in"))
      (node (ref "MOD_6") (pin "V20") (pinfunction "GND_V20") (pintype "power_in"))
      (node (ref "MOD_6") (pin "V21") (pinfunction "GND_V21") (pintype "power_in"))
      (node (ref "MOD_6") (pin "V22") (pinfunction "GND_V22") (pintype "power_in"))
      (node (ref "MOD_6") (pin "V23") (pinfunction "GND_V23") (pintype "power_in"))
      (node (ref "MOD_6") (pin "V24") (pinfunction "GND_V24") (pintype "power_in"))
      (node (ref "MOD_6") (pin "V25") (pinfunction "GND_V25") (pintype "power_in"))
      (node (ref "MOD_6") (pin "V26") (pinfunction "GND_V26") (pintype "power_in"))
      (node (ref "MOD_6") (pin "V27") (pinfunction "GND_V27") (pintype "power_in"))
      (node (ref "MOD_6") (pin "V28") (pinfunction "GND_V28") (pintype "power_in"))
      (node (ref "MOD_6") (pin "V29") (pinfunction "GND_V29") (pintype "power_in"))
      (node (ref "MOD_6") (pin "V3") (pinfunction "GND_V3") (pintype "power_in"))
      (node (ref "MOD_6") (pin "V30") (pinfunction "GND_V30") (pintype "power_in"))
      (node (ref "MOD_6") (pin "V4") (pinfunction "GND_V4") (pintype "power_in"))
      (node (ref "MOD_6") (pin "V5") (pinfunction "GND_V5") (pintype "power_in"))
      (node (ref "MOD_6") (pin "V6") (pinfunction "GND_V6") (pintype "power_in"))
      (node (ref "MOD_6") (pin "V7") (pinfunction "GND_V7") (pintype "power_in"))
      (node (ref "MOD_6") (pin "V8") (pinfunction "GND_V8") (pintype "power_in"))
      (node (ref "MOD_6") (pin "V9") (pinfunction "GND_V9") (pintype "power_in"))
      (node (ref "R10") (pin "1") (pinfunction "1_1") (pintype "passive"))
      (node (ref "R10") (pin "2") (pinfunction "2_2") (pintype "passive"))
      (node (ref "R11") (pin "1") (pinfunction "1_1") (pintype "passive"))
      (node (ref "R11") (pin "2") (pinfunction "2_2") (pintype "passive"))
      (node (ref "R8") (pin "1") (pinfunction "1_1") (pintype "passive"))
      (node (ref "R8") (pin "2") (pinfunction "2_2") (pintype "passive"))
      (node (ref "R9") (pin "1") (pinfunction "1_1") (pintype "passive"))
    )
    (net (code "25") (name "Net-(IC7-BYP)") (class "Default")
      (node (ref "C9") (pin "1") (pinfunction "1_1") (pintype "passive"))
      (node (ref "IC7") (pin "4") (pinfunction "BYP_4") (pintype "bidirectional"))
    )
    (net (code "26") (name "Net-(IC7-EN)") (class "Default")
      (node (ref "C8") (pin "1") (pinfunction "1_1") (pintype "passive"))
      (node (ref "D1") (pin "C") (pinfunction "C_C") (pintype "passive"))
      (node (ref "IC7") (pin "1") (pinfunction "IN_1") (pintype "power_in"))
      (node (ref "IC7") (pin "3") (pinfunction "EN_3") (pintype "input"))
      (node (ref "IC8") (pin "1") (pinfunction "IN_1") (pintype "power_in"))
      (node (ref "IC8") (pin "3") (pinfunction "EN_3") (pintype "input"))
      (node (ref "R7") (pin "1") (pinfunction "1_1") (pintype "passive"))
    )
    (net (code "27") (name "Net-(IC8-BYP)") (class "Default")
      (node (ref "C11") (pin "1") (pinfunction "1_1") (pintype "passive"))
      (node (ref "IC8") (pin "4") (pinfunction "BYP_4") (pintype "bidirectional"))
    )
    (net (code "28") (name "unconnected-(CON1-Pad2)") (class "Default")
      (node (ref "CON1") (pin "2") (pinfunction "2_2") (pintype "passive"))
    )
    (net (code "29") (name "unconnected-(IC1-RO-Pad2)") (class "Default")
      (node (ref "IC1") (pin "2") (pinfunction "RO_2") (pintype "output"))
    )
    (net (code "30") (name "unconnected-(IC2-RO-Pad2)") (class "Default")
      (node (ref "IC2") (pin "2") (pinfunction "RO_2") (pintype "output"))
    )
    (net (code "31") (name "unconnected-(IC3-RO-Pad2)") (class "Default")
      (node (ref "IC3") (pin "2") (pinfunction "RO_2") (pintype "output"))
    )
    (net (code "32") (name "unconnected-(IC4-RO-Pad2)") (class "Default")
      (node (ref "IC4") (pin "2") (pinfunction "RO_2") (pintype "output"))
    )
    (net (code "33") (name "unconnected-(IC5-RO-Pad2)") (class "Default")
      (node (ref "IC5") (pin "2") (pinfunction "RO_2") (pintype "output"))
    )
    (net (code "34") (name "unconnected-(IC6-RO-Pad2)") (class "Default")
      (node (ref "IC6") (pin "2") (pinfunction "RO_2") (pintype "output"))
    )
  )
)
